# PX4Isolator.net
KiCad netlist of a schematic drawn in EAGLE
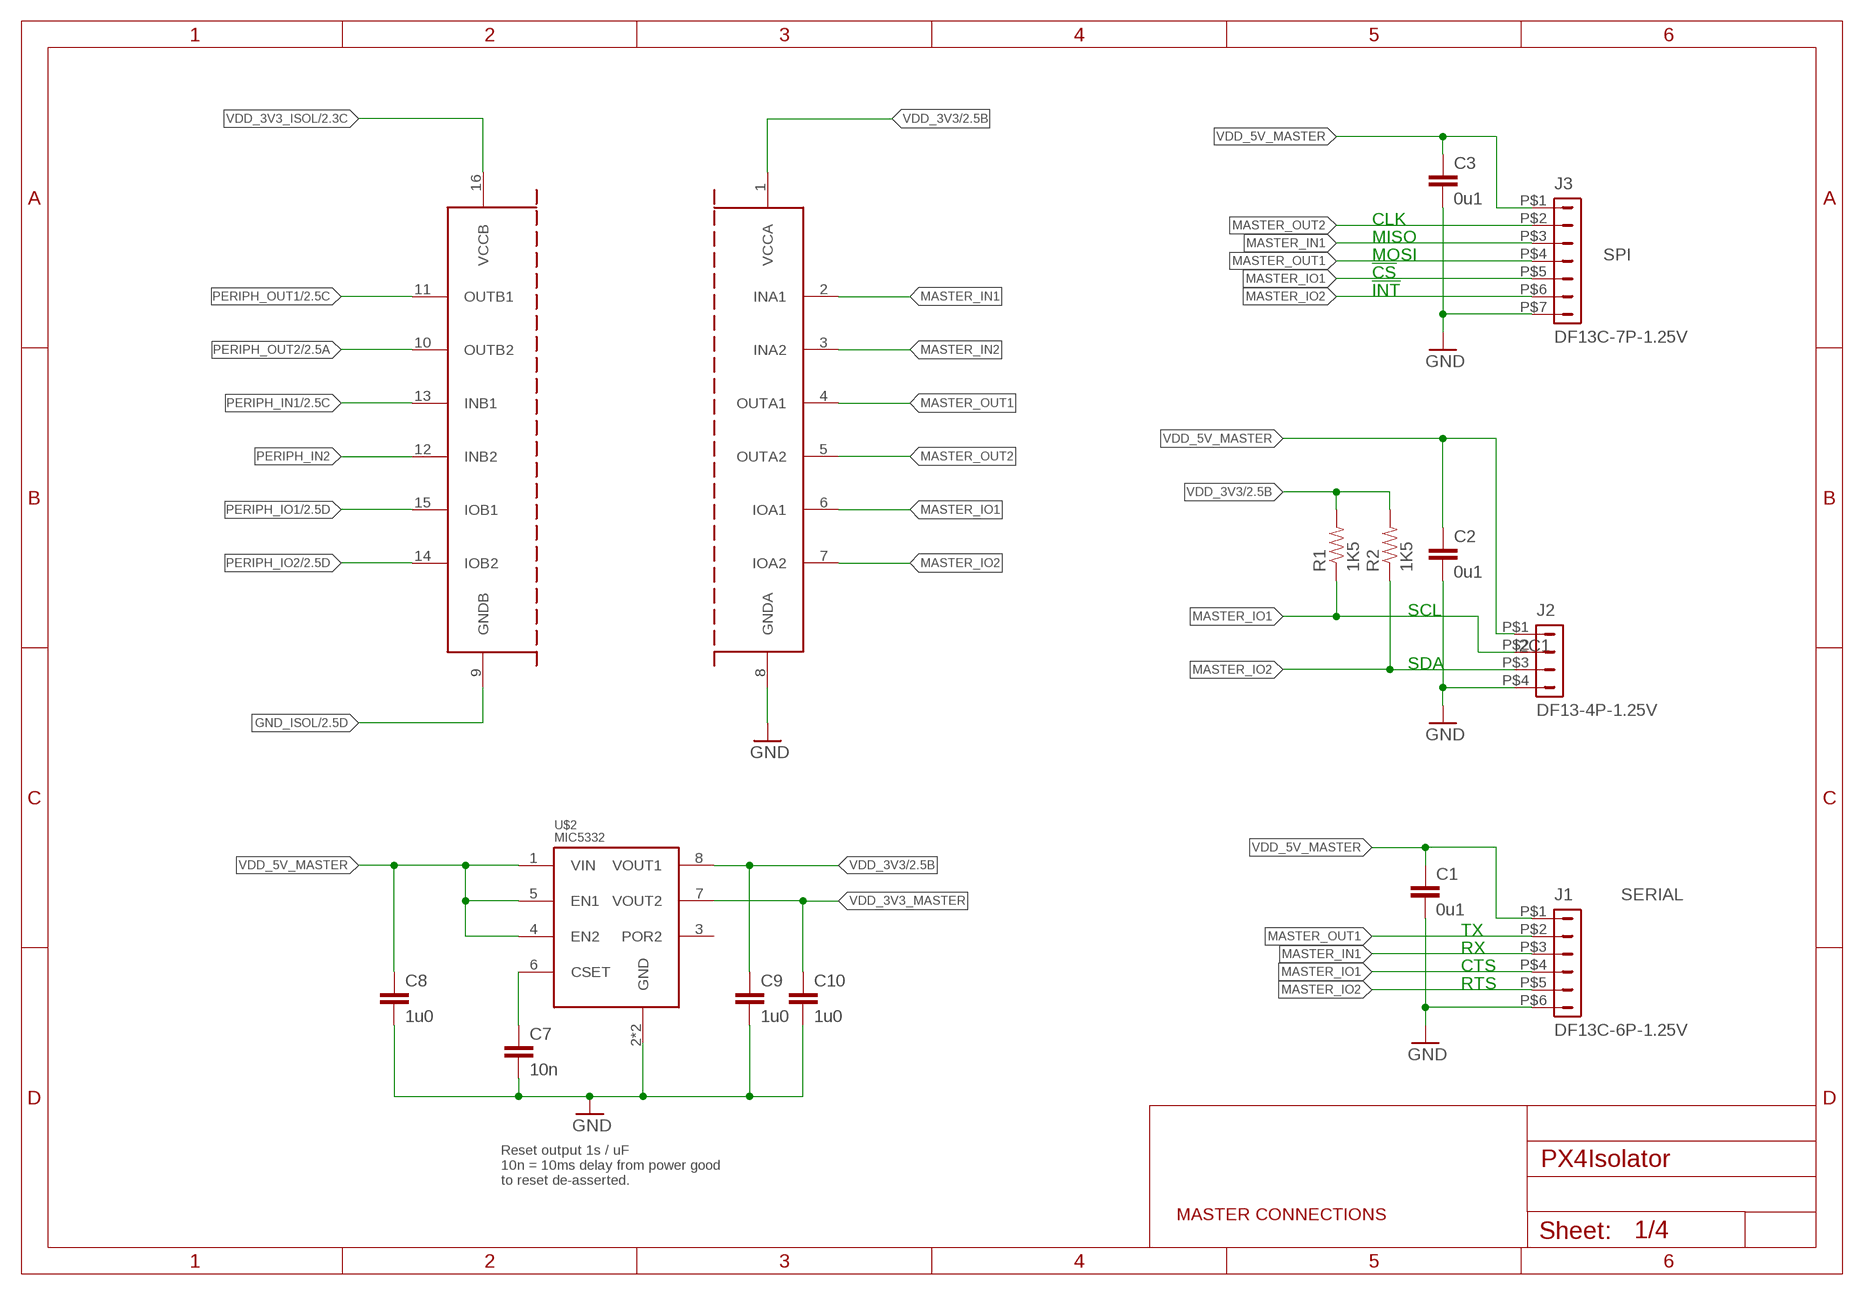
[diagram p0: schematic, sheet 1]
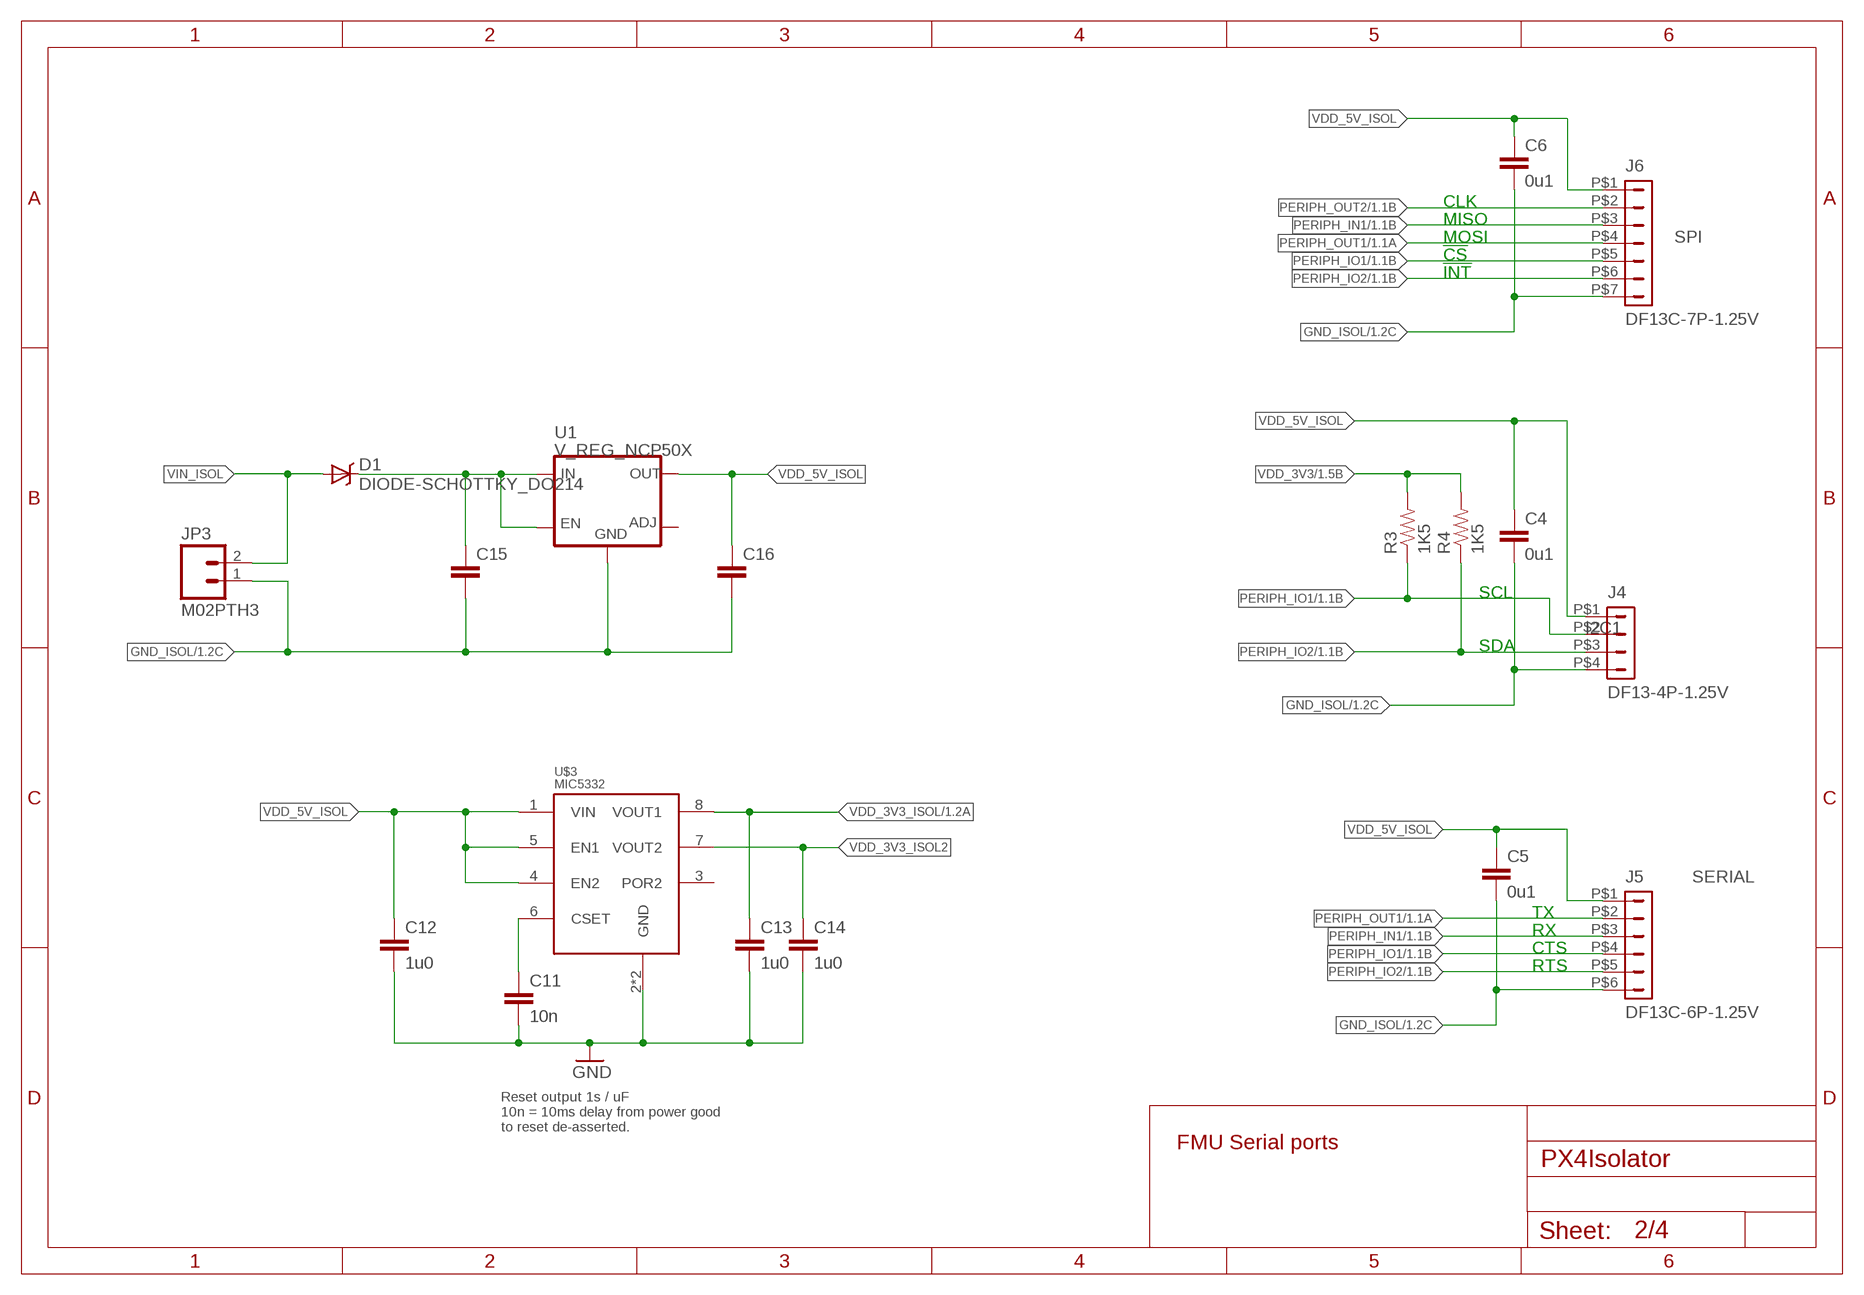
[diagram p1: schematic, sheet 2]
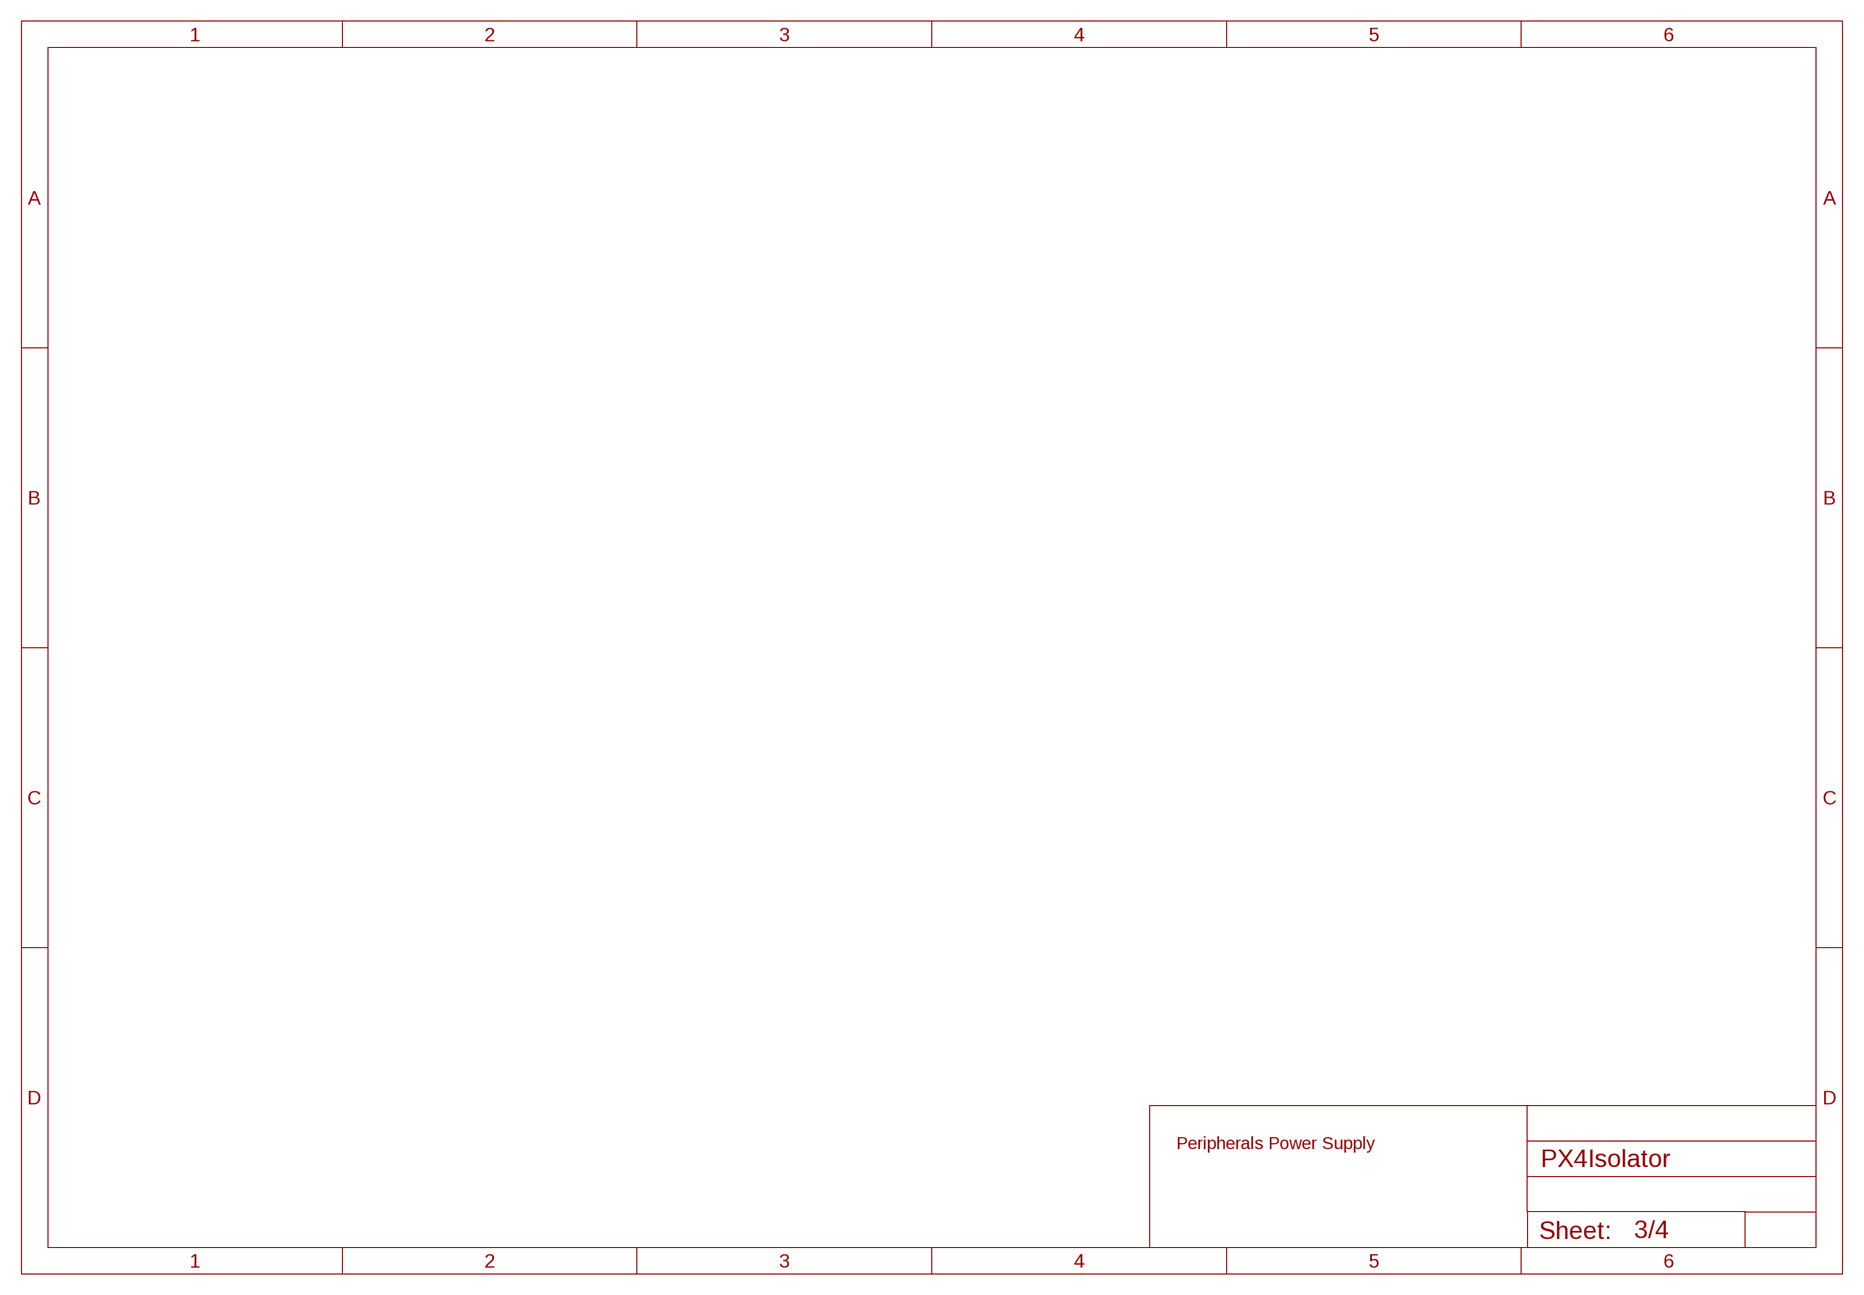
[diagram p2: schematic, sheet 3]
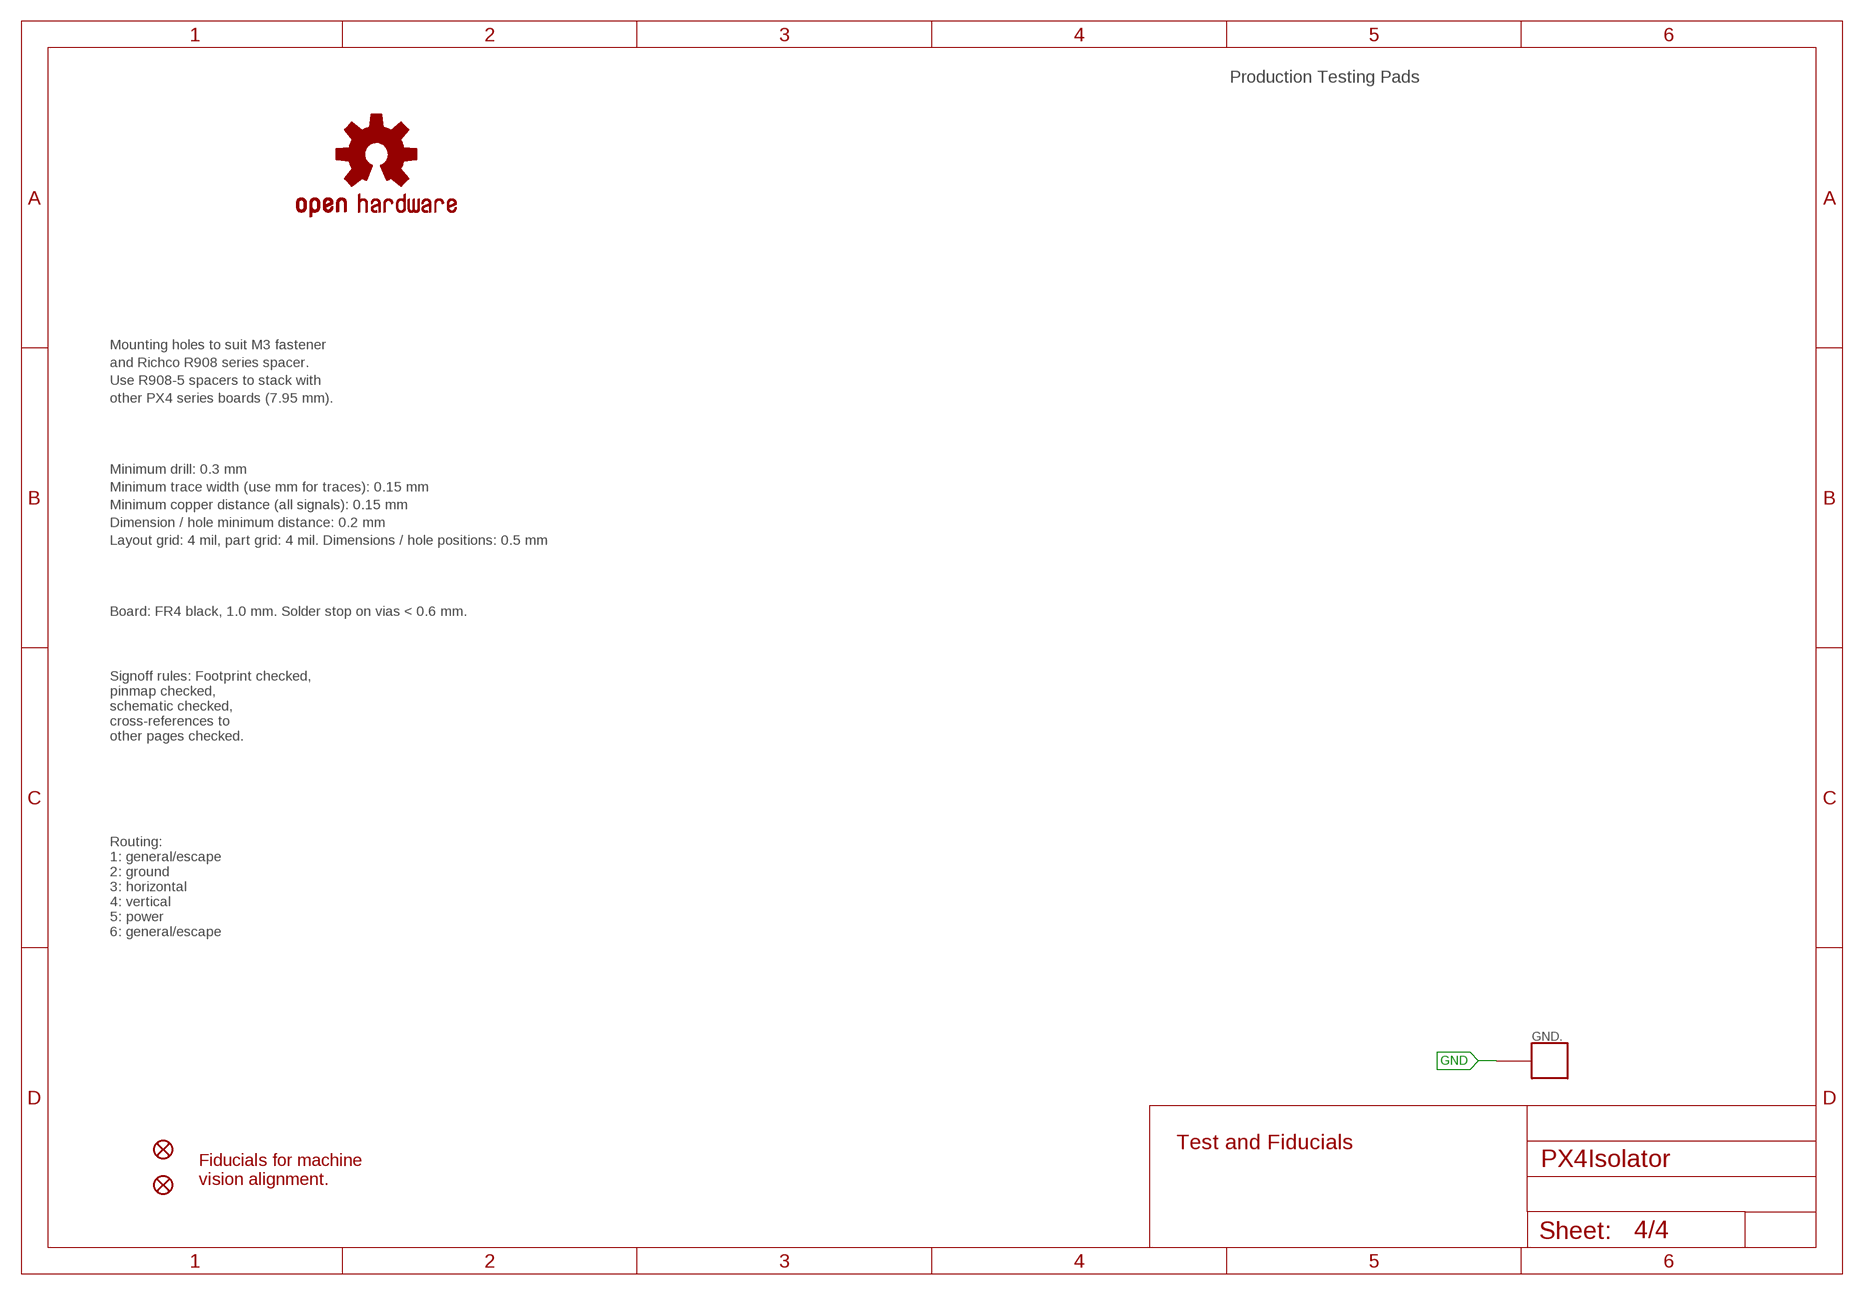
[diagram p3: schematic, sheet 4]

(export (version "E")
  (design (tool "Eeschema 10.0.6"))
  (components
    (comp (ref "C1")
      (value "0u1")
      (footprint "eagle-import:0402-CAP")
      (fields (field (name "PARTNO") "CC0402ZRY5V7BB104"))
      (libsource (lib "eagle-import") (part "pixhawk2_CAP0402"))
    )
    (comp (ref "C2")
      (value "0u1")
      (footprint "eagle-import:0402-CAP")
      (fields (field (name "PARTNO") "CC0402ZRY5V7BB104"))
      (libsource (lib "eagle-import") (part "pixhawk2_CAP0402"))
    )
    (comp (ref "C3")
      (value "0u1")
      (footprint "eagle-import:0402-CAP")
      (fields (field (name "PARTNO") "CC0402ZRY5V7BB104"))
      (libsource (lib "eagle-import") (part "pixhawk2_CAP0402"))
    )
    (comp (ref "C7")
      (value "10n")
      (footprint "eagle-import:0402-CAP")
      (fields (field (name "PARTNO") "CC0402KRX7R7BB103"))
      (libsource (lib "eagle-import") (part "pixhawk2_CAP0402"))
    )
    (comp (ref "C8")
      (value "1u0")
      (footprint "eagle-import:0603-CAP")
      (fields (field (name "PARTNO") "CC0603ZRY5V7BB105"))
      (libsource (lib "eagle-import") (part "pixhawk2_CAP0603"))
    )
    (comp (ref "C9")
      (value "1u0")
      (footprint "eagle-import:0603-CAP")
      (fields (field (name "PARTNO") "CC0603ZRY5V7BB105"))
      (libsource (lib "eagle-import") (part "pixhawk2_CAP0603"))
    )
    (comp (ref "C10")
      (value "1u0")
      (footprint "eagle-import:0603-CAP")
      (fields (field (name "PARTNO") "CC0603ZRY5V7BB105"))
      (libsource (lib "eagle-import") (part "pixhawk2_CAP0603"))
    )
    (comp (ref "J1")
      (value "DF13C-6P-1.25V")
      (footprint "eagle-import:DF13C-6P-1.25V")
      (fields (field (name "PARTNO") "DF13C-6P-1.25V(20)"))
      (libsource (lib "eagle-import") (part "DF13-6P-1.25V"))
    )
    (comp (ref "J2")
      (value "DF13-4P-1.25V")
      (footprint "eagle-import:DF13C-4P-1.25V")
      (fields (field (name "PARTNO") "DF13C-4P-1.25V(20)"))
      (libsource (lib "eagle-import") (part "DF13-4P-1.25V"))
    )
    (comp (ref "J3")
      (value "DF13C-7P-1.25V")
      (footprint "eagle-import:DF13C-7P-1.25V")
      (fields (field (name "PARTNO") "DF13C-7P-1.25V(20)"))
      (libsource (lib "eagle-import") (part "DF13-7P-1.25V"))
    )
    (comp (ref "R1")
      (value "1K5")
      (footprint "eagle-import:0402-RES")
      (fields (field (name "PARTNO") "RC0402FR-071K5L"))
      (libsource (lib "eagle-import") (part "RESISTOR0402-RES"))
    )
    (comp (ref "R2")
      (value "1K5")
      (footprint "eagle-import:0402-RES")
      (fields (field (name "PARTNO") "RC0402FR-071K5L"))
      (libsource (lib "eagle-import") (part "RESISTOR0402-RES"))
    )
    (comp (ref "U$1")
      (value "MAX14850")
      (footprint "eagle-import:SOIC16")
      (libsource (lib "eagle-import") (part "MAX14850"))
    )
    (comp (ref "U$2")
      (value "MIC5332")
      (footprint "eagle-import:MLF-8-EPAD")
      (fields (field (name "PARTNO") "MIC5332-SSYMT"))
      (libsource (lib "eagle-import") (part "MIC5332"))
    )
    (comp (ref "C4")
      (value "0u1")
      (footprint "eagle-import:0402-CAP")
      (fields (field (name "PARTNO") "CC0402ZRY5V7BB104"))
      (libsource (lib "eagle-import") (part "pixhawk2_CAP0402"))
    )
    (comp (ref "C5")
      (value "0u1")
      (footprint "eagle-import:0402-CAP")
      (fields (field (name "PARTNO") "CC0402ZRY5V7BB104"))
      (libsource (lib "eagle-import") (part "pixhawk2_CAP0402"))
    )
    (comp (ref "C6")
      (value "0u1")
      (footprint "eagle-import:0402-CAP")
      (fields (field (name "PARTNO") "CC0402ZRY5V7BB104"))
      (libsource (lib "eagle-import") (part "pixhawk2_CAP0402"))
    )
    (comp (ref "C11")
      (value "10n")
      (footprint "eagle-import:0402-CAP")
      (fields (field (name "PARTNO") "CC0402KRX7R7BB103"))
      (libsource (lib "eagle-import") (part "pixhawk2_CAP0402"))
    )
    (comp (ref "C12")
      (value "1u0")
      (footprint "eagle-import:0603-CAP")
      (fields (field (name "PARTNO") "CC0603ZRY5V7BB105"))
      (libsource (lib "eagle-import") (part "pixhawk2_CAP0603"))
    )
    (comp (ref "C13")
      (value "1u0")
      (footprint "eagle-import:0603-CAP")
      (fields (field (name "PARTNO") "CC0603ZRY5V7BB105"))
      (libsource (lib "eagle-import") (part "pixhawk2_CAP0603"))
    )
    (comp (ref "C14")
      (value "1u0")
      (footprint "eagle-import:0603-CAP")
      (fields (field (name "PARTNO") "CC0603ZRY5V7BB105"))
      (libsource (lib "eagle-import") (part "pixhawk2_CAP0603"))
    )
    (comp (ref "C15")
      (value "CAP0603")
      (footprint "eagle-import:0603-CAP")
      (libsource (lib "eagle-import") (part "CAP0603"))
    )
    (comp (ref "C16")
      (value "CAP0603")
      (footprint "eagle-import:0603-CAP")
      (libsource (lib "eagle-import") (part "CAP0603"))
    )
    (comp (ref "D1")
      (value "DIODE-SCHOTTKY_DO214")
      (footprint "eagle-import:DO214AC")
      (libsource (lib "eagle-import") (part "DIODE-SCHOTTKY_DO214"))
    )
    (comp (ref "J4")
      (value "DF13-4P-1.25V")
      (footprint "eagle-import:DF13C-4P-1.25V")
      (fields (field (name "PARTNO") "DF13C-4P-1.25V(20)"))
      (libsource (lib "eagle-import") (part "DF13-4P-1.25V"))
    )
    (comp (ref "J5")
      (value "DF13C-6P-1.25V")
      (footprint "eagle-import:DF13C-6P-1.25V")
      (fields (field (name "PARTNO") "DF13C-6P-1.25V(20)"))
      (libsource (lib "eagle-import") (part "DF13-6P-1.25V"))
    )
    (comp (ref "J6")
      (value "DF13C-7P-1.25V")
      (footprint "eagle-import:DF13C-7P-1.25V")
      (fields (field (name "PARTNO") "DF13C-7P-1.25V(20)"))
      (libsource (lib "eagle-import") (part "DF13-7P-1.25V"))
    )
    (comp (ref "JP3")
      (value "M02PTH3")
      (footprint "eagle-import:1X02_LONGPADS")
      (libsource (lib "eagle-import") (part "M02PTH3"))
    )
    (comp (ref "R3")
      (value "1K5")
      (footprint "eagle-import:0402-RES")
      (fields (field (name "PARTNO") "RC0402FR-071K5L"))
      (libsource (lib "eagle-import") (part "RESISTOR0402-RES"))
    )
    (comp (ref "R4")
      (value "1K5")
      (footprint "eagle-import:0402-RES")
      (fields (field (name "PARTNO") "RC0402FR-071K5L"))
      (libsource (lib "eagle-import") (part "RESISTOR0402-RES"))
    )
    (comp (ref "U$3")
      (value "MIC5332")
      (footprint "eagle-import:MLF-8-EPAD")
      (fields (field (name "PARTNO") "MIC5332-SSYMT"))
      (libsource (lib "eagle-import") (part "MIC5332"))
    )
    (comp (ref "U1")
      (value "V_REG_NCP50X")
      (footprint "eagle-import:DPAK-5")
      (libsource (lib "eagle-import") (part "V_REG_NCP50X"))
    )
    (comp (ref "GND.")
      (value "PAD.04")
      (footprint "eagle-import:PAD.04X.04")
      (libsource (lib "eagle-import") (part "PAD.04"))
    )
    (comp (ref "JP1")
      (value "FIDUCIAL1.5X3")
      (footprint "eagle-import:FIDUCIAL-1.5X3")
      (libsource (lib "eagle-import") (part "FIDUCIAL1.5X3"))
    )
    (comp (ref "JP2")
      (value "FIDUCIAL1.5X3")
      (footprint "eagle-import:FIDUCIAL-1.5X3")
      (libsource (lib "eagle-import") (part "FIDUCIAL1.5X3"))
    )
    (comp (ref "OSHW_LOGO")
      (value "OSHW-LOGOS")
      (footprint "eagle-import:OSHW-LOGO-S")
      (libsource (lib "eagle-import") (part "OSHW-LOGOS"))
    )
  )
  (nets
    (net (code "1") (name "GND") (class "Default")
      (node (ref "C1") (pin "P$2") (pinfunction "2_P$2") (pintype "passive"))
      (node (ref "C10") (pin "P$2") (pinfunction "2_P$2") (pintype "passive"))
      (node (ref "C11") (pin "P$2") (pinfunction "2_P$2") (pintype "passive"))
      (node (ref "C12") (pin "P$2") (pinfunction "2_P$2") (pintype "passive"))
      (node (ref "C13") (pin "P$2") (pinfunction "2_P$2") (pintype "passive"))
      (node (ref "C14") (pin "P$2") (pinfunction "2_P$2") (pintype "passive"))
      (node (ref "C2") (pin "P$2") (pinfunction "2_P$2") (pintype "passive"))
      (node (ref "C3") (pin "P$2") (pinfunction "2_P$2") (pintype "passive"))
      (node (ref "C7") (pin "P$2") (pinfunction "2_P$2") (pintype "passive"))
      (node (ref "C8") (pin "P$2") (pinfunction "2_P$2") (pintype "passive"))
      (node (ref "C9") (pin "P$2") (pinfunction "2_P$2") (pintype "passive"))
      (node (ref "GND.") (pin "P$1") (pinfunction "P$1_P$1") (pintype "passive"))
      (node (ref "J1") (pin "P$6") (pinfunction "6_P$6") (pintype "passive"))
      (node (ref "J2") (pin "P$4") (pinfunction "4_P$4") (pintype "passive"))
      (node (ref "J3") (pin "P$7") (pinfunction "7_P$7") (pintype "passive"))
      (node (ref "U$1") (pin "8") (pinfunction "GNDA_8") (pintype "power_in"))
      (node (ref "U$2") (pin "2") (pinfunction "GND_2") (pintype "bidirectional"))
      (node (ref "U$2") (pin "GND") (pinfunction "GND_GND") (pintype "bidirectional"))
      (node (ref "U$3") (pin "2") (pinfunction "GND_2") (pintype "bidirectional"))
      (node (ref "U$3") (pin "GND") (pinfunction "GND_GND") (pintype "bidirectional"))
    )
    (net (code "2") (name "GND_ISOL") (class "Default")
      (node (ref "C15") (pin "P$2") (pinfunction "2_P$2") (pintype "passive"))
      (node (ref "C16") (pin "P$2") (pinfunction "2_P$2") (pintype "passive"))
      (node (ref "C4") (pin "P$2") (pinfunction "2_P$2") (pintype "passive"))
      (node (ref "C5") (pin "P$2") (pinfunction "2_P$2") (pintype "passive"))
      (node (ref "C6") (pin "P$2") (pinfunction "2_P$2") (pintype "passive"))
      (node (ref "J4") (pin "P$4") (pinfunction "4_P$4") (pintype "passive"))
      (node (ref "J5") (pin "P$6") (pinfunction "6_P$6") (pintype "passive"))
      (node (ref "J6") (pin "P$7") (pinfunction "7_P$7") (pintype "passive"))
      (node (ref "JP3") (pin "1") (pinfunction "1_1") (pintype "passive"))
      (node (ref "U$1") (pin "9") (pinfunction "GNDB_9") (pintype "power_in"))
      (node (ref "U1") (pin "GND") (pinfunction "GND_GND") (pintype "bidirectional"))
    )
    (net (code "3") (name "MASTER_IN1") (class "Default")
      (node (ref "J1") (pin "P$3") (pinfunction "3_P$3") (pintype "passive"))
      (node (ref "J3") (pin "P$3") (pinfunction "3_P$3") (pintype "passive"))
      (node (ref "U$1") (pin "2") (pinfunction "INA1_2") (pintype "bidirectional"))
    )
    (net (code "4") (name "MASTER_IN2") (class "Default")
      (node (ref "U$1") (pin "3") (pinfunction "INA2_3") (pintype "bidirectional"))
    )
    (net (code "5") (name "MASTER_IO1") (class "Default")
      (node (ref "J1") (pin "P$4") (pinfunction "4_P$4") (pintype "passive"))
      (node (ref "J2") (pin "P$2") (pinfunction "2_P$2") (pintype "passive"))
      (node (ref "J3") (pin "P$5") (pinfunction "5_P$5") (pintype "passive"))
      (node (ref "R1") (pin "P$1") (pinfunction "1_P$1") (pintype "passive"))
      (node (ref "U$1") (pin "6") (pinfunction "IOA1_6") (pintype "bidirectional"))
    )
    (net (code "6") (name "MASTER_IO2") (class "Default")
      (node (ref "J1") (pin "P$5") (pinfunction "5_P$5") (pintype "passive"))
      (node (ref "J2") (pin "P$3") (pinfunction "3_P$3") (pintype "passive"))
      (node (ref "J3") (pin "P$6") (pinfunction "6_P$6") (pintype "passive"))
      (node (ref "R2") (pin "P$1") (pinfunction "1_P$1") (pintype "passive"))
      (node (ref "U$1") (pin "7") (pinfunction "IOA2_7") (pintype "bidirectional"))
    )
    (net (code "7") (name "MASTER_OUT1") (class "Default")
      (node (ref "J1") (pin "P$2") (pinfunction "2_P$2") (pintype "passive"))
      (node (ref "J3") (pin "P$4") (pinfunction "4_P$4") (pintype "passive"))
      (node (ref "U$1") (pin "4") (pinfunction "OUTA1_4") (pintype "bidirectional"))
    )
    (net (code "8") (name "MASTER_OUT2") (class "Default")
      (node (ref "J3") (pin "P$2") (pinfunction "2_P$2") (pintype "passive"))
      (node (ref "U$1") (pin "5") (pinfunction "OUTA2_5") (pintype "bidirectional"))
    )
    (net (code "9") (name "Net-(C7-1)") (class "Default")
      (node (ref "C7") (pin "P$1") (pinfunction "1_P$1") (pintype "passive"))
      (node (ref "U$2") (pin "6") (pinfunction "CSET_6") (pintype "bidirectional"))
    )
    (net (code "10") (name "Net-(C11-1)") (class "Default")
      (node (ref "C11") (pin "P$1") (pinfunction "1_P$1") (pintype "passive"))
      (node (ref "U$3") (pin "6") (pinfunction "CSET_6") (pintype "bidirectional"))
    )
    (net (code "11") (name "Net-(C15-1)") (class "Default")
      (node (ref "C15") (pin "P$1") (pinfunction "1_P$1") (pintype "passive"))
      (node (ref "D1") (pin "C") (pinfunction "C_C") (pintype "passive"))
      (node (ref "U1") (pin "EN") (pinfunction "EN_EN") (pintype "bidirectional"))
      (node (ref "U1") (pin "VIN") (pinfunction "IN_VIN") (pintype "input"))
    )
    (net (code "12") (name "PERIPH_IN1") (class "Default")
      (node (ref "J5") (pin "P$3") (pinfunction "3_P$3") (pintype "passive"))
      (node (ref "J6") (pin "P$3") (pinfunction "3_P$3") (pintype "passive"))
      (node (ref "U$1") (pin "13") (pinfunction "INB1_13") (pintype "bidirectional"))
    )
    (net (code "13") (name "PERIPH_IN2") (class "Default")
      (node (ref "U$1") (pin "12") (pinfunction "INB2_12") (pintype "bidirectional"))
    )
    (net (code "14") (name "PERIPH_IO1") (class "Default")
      (node (ref "J4") (pin "P$2") (pinfunction "2_P$2") (pintype "passive"))
      (node (ref "J5") (pin "P$4") (pinfunction "4_P$4") (pintype "passive"))
      (node (ref "J6") (pin "P$5") (pinfunction "5_P$5") (pintype "passive"))
      (node (ref "R3") (pin "P$1") (pinfunction "1_P$1") (pintype "passive"))
      (node (ref "U$1") (pin "15") (pinfunction "IOB1_15") (pintype "bidirectional"))
    )
    (net (code "15") (name "PERIPH_IO2") (class "Default")
      (node (ref "J4") (pin "P$3") (pinfunction "3_P$3") (pintype "passive"))
      (node (ref "J5") (pin "P$5") (pinfunction "5_P$5") (pintype "passive"))
      (node (ref "J6") (pin "P$6") (pinfunction "6_P$6") (pintype "passive"))
      (node (ref "R4") (pin "P$1") (pinfunction "1_P$1") (pintype "passive"))
      (node (ref "U$1") (pin "14") (pinfunction "IOB2_14") (pintype "bidirectional"))
    )
    (net (code "16") (name "PERIPH_OUT1") (class "Default")
      (node (ref "J5") (pin "P$2") (pinfunction "2_P$2") (pintype "passive"))
      (node (ref "J6") (pin "P$4") (pinfunction "4_P$4") (pintype "passive"))
      (node (ref "U$1") (pin "11") (pinfunction "OUTB1_11") (pintype "bidirectional"))
    )
    (net (code "17") (name "PERIPH_OUT2") (class "Default")
      (node (ref "J6") (pin "P$2") (pinfunction "2_P$2") (pintype "passive"))
      (node (ref "U$1") (pin "10") (pinfunction "OUTB2_10") (pintype "bidirectional"))
    )
    (net (code "18") (name "VDD_3V3") (class "Default")
      (node (ref "C9") (pin "P$1") (pinfunction "1_P$1") (pintype "passive"))
      (node (ref "R1") (pin "P$2") (pinfunction "2_P$2") (pintype "passive"))
      (node (ref "R2") (pin "P$2") (pinfunction "2_P$2") (pintype "passive"))
      (node (ref "R3") (pin "P$2") (pinfunction "2_P$2") (pintype "passive"))
      (node (ref "R4") (pin "P$2") (pinfunction "2_P$2") (pintype "passive"))
      (node (ref "U$1") (pin "1") (pinfunction "VCCA_1") (pintype "power_in"))
      (node (ref "U$2") (pin "8") (pinfunction "VOUT1_8") (pintype "bidirectional"))
    )
    (net (code "19") (name "VDD_3V3_ISOL") (class "Default")
      (node (ref "C13") (pin "P$1") (pinfunction "1_P$1") (pintype "passive"))
      (node (ref "U$1") (pin "16") (pinfunction "VCCB_16") (pintype "power_in"))
      (node (ref "U$3") (pin "8") (pinfunction "VOUT1_8") (pintype "bidirectional"))
    )
    (net (code "20") (name "VDD_3V3_ISOL2") (class "Default")
      (node (ref "C14") (pin "P$1") (pinfunction "1_P$1") (pintype "passive"))
      (node (ref "U$3") (pin "7") (pinfunction "VOUT2_7") (pintype "bidirectional"))
    )
    (net (code "21") (name "VDD_3V3_MASTER") (class "Default")
      (node (ref "C10") (pin "P$1") (pinfunction "1_P$1") (pintype "passive"))
      (node (ref "U$2") (pin "7") (pinfunction "VOUT2_7") (pintype "bidirectional"))
    )
    (net (code "22") (name "VDD_5V_ISOL") (class "Default")
      (node (ref "C12") (pin "P$1") (pinfunction "1_P$1") (pintype "passive"))
      (node (ref "C16") (pin "P$1") (pinfunction "1_P$1") (pintype "passive"))
      (node (ref "C4") (pin "P$1") (pinfunction "1_P$1") (pintype "passive"))
      (node (ref "C5") (pin "P$1") (pinfunction "1_P$1") (pintype "passive"))
      (node (ref "C6") (pin "P$1") (pinfunction "1_P$1") (pintype "passive"))
      (node (ref "J4") (pin "P$1") (pinfunction "1_P$1") (pintype "passive"))
      (node (ref "J5") (pin "P$1") (pinfunction "1_P$1") (pintype "passive"))
      (node (ref "J6") (pin "P$1") (pinfunction "1_P$1") (pintype "passive"))
      (node (ref "U$3") (pin "1") (pinfunction "VIN_1") (pintype "bidirectional"))
      (node (ref "U$3") (pin "4") (pinfunction "EN2_4") (pintype "bidirectional"))
      (node (ref "U$3") (pin "5") (pinfunction "EN1_5") (pintype "bidirectional"))
      (node (ref "U1") (pin "VOUT") (pinfunction "OUT_VOUT") (pintype "output"))
    )
    (net (code "23") (name "VDD_5V_MASTER") (class "Default")
      (node (ref "C1") (pin "P$1") (pinfunction "1_P$1") (pintype "passive"))
      (node (ref "C2") (pin "P$1") (pinfunction "1_P$1") (pintype "passive"))
      (node (ref "C3") (pin "P$1") (pinfunction "1_P$1") (pintype "passive"))
      (node (ref "C8") (pin "P$1") (pinfunction "1_P$1") (pintype "passive"))
      (node (ref "J1") (pin "P$1") (pinfunction "1_P$1") (pintype "passive"))
      (node (ref "J2") (pin "P$1") (pinfunction "1_P$1") (pintype "passive"))
      (node (ref "J3") (pin "P$1") (pinfunction "1_P$1") (pintype "passive"))
      (node (ref "U$2") (pin "1") (pinfunction "VIN_1") (pintype "bidirectional"))
      (node (ref "U$2") (pin "4") (pinfunction "EN2_4") (pintype "bidirectional"))
      (node (ref "U$2") (pin "5") (pinfunction "EN1_5") (pintype "bidirectional"))
    )
    (net (code "24") (name "VIN_ISOL") (class "Default")
      (node (ref "D1") (pin "A") (pinfunction "A_A") (pintype "passive"))
      (node (ref "JP3") (pin "2") (pinfunction "2_2") (pintype "passive"))
    )
    (net (code "25") (name "unconnected-(U$2-POR2-Pad3)") (class "Default")
      (node (ref "U$2") (pin "3") (pinfunction "POR2_3") (pintype "bidirectional"))
    )
    (net (code "26") (name "unconnected-(U$3-POR2-Pad3)") (class "Default")
      (node (ref "U$3") (pin "3") (pinfunction "POR2_3") (pintype "bidirectional"))
    )
    (net (code "27") (name "unconnected-(U1-PadADJ)") (class "Default")
      (node (ref "U1") (pin "ADJ") (pinfunction "ADJ_ADJ") (pintype "input"))
    )
  )
)
